# WiFi.net
KiCad netlist of a schematic drawn in Altium Designer
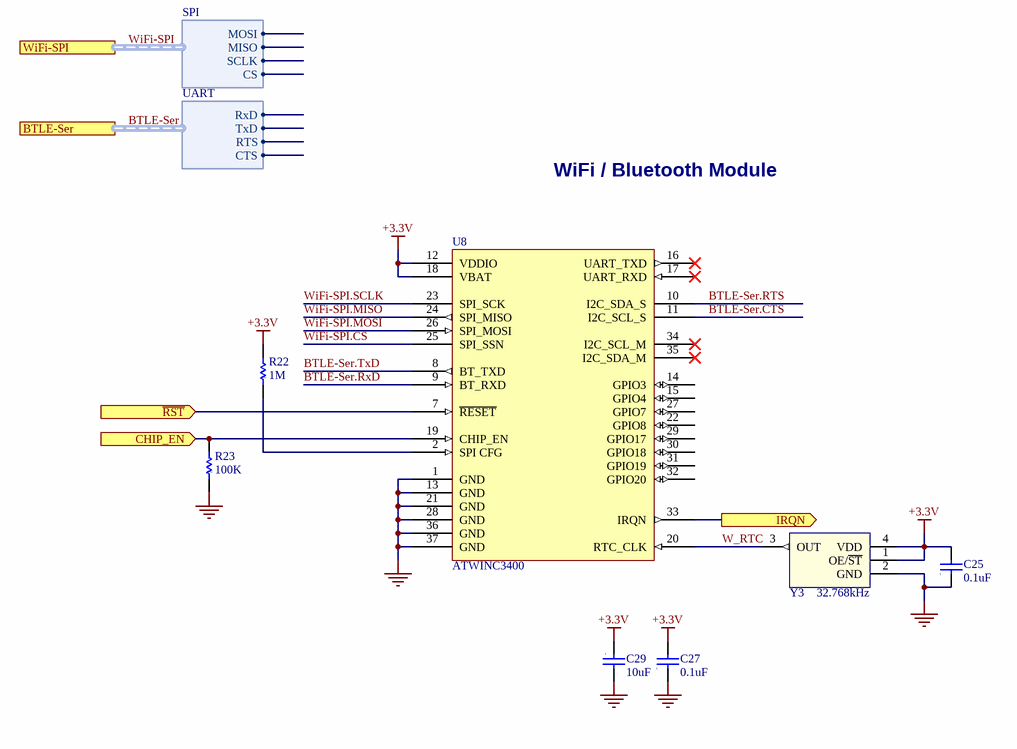
[diagram p0: WiFi.SchDoc]

(export (version "E")
  (design (tool "Eeschema 10.0.6"))
  (components
    (comp (ref "C25")
      (value "0.1uF")
      (footprint "0402")
      (description "CAP CER .10UF 50V X7R 10% 0402")
      (fields
        (field (name "MANUFACTURER") "TDK Corporation")
        (field (name "MANUFACTURER PART NUMBER") "C1005X7R1H104K")
        (field (name "PUBLISHER") "Altium Limited")
      )
      (libsource (lib "") (part "Cap_1"))
    )
    (comp (ref "C27")
      (value "0.1uF")
      (footprint "0402")
      (description "CAP CER .10UF 50V X7R 10% 0402")
      (fields
        (field (name "MANUFACTURER") "TDK Corporation")
        (field (name "MANUFACTURER PART NUMBER") "C1005X7R1H104K")
        (field (name "PUBLISHER") "Altium Limited")
      )
      (libsource (lib "") (part "Cap_1"))
    )
    (comp (ref "C29")
      (value "10uF")
      (footprint "0805")
      (description "CAP CER 10UF 35V X5R 0805")
      (fields
        (field (name "MANUFACTURER") "TDK")
        (field (name "MANUFACTURER PART NUMBER") "C2012X5R1V106K085AC")
        (field (name "PUBLISHER") "Altium Limited")
      )
      (libsource (lib "General") (part "Cap"))
    )
    (comp (ref "R22")
      (value "1M")
      (footprint "R0402")
      (description "RES SMD 1M OHM 5% 1/10W 0402")
      (fields
        (field (name "MANUFACTURER") "Panasonic")
        (field (name "MANUFACTURER PART NUMBER") "ERJ-2GEJ105X")
      )
      (libsource (lib "General") (part "Res"))
    )
    (comp (ref "R23")
      (value "100K")
      (footprint "R0402")
      (description "RES SMD 100K OHM 1% 1/16W 0402")
      (fields
        (field (name "MANUFACTURER") "Panasonic")
        (field (name "MANUFACTURER PART NUMBER") "ERJ-2RKF1003X")
      )
      (libsource (lib "General") (part "Res"))
    )
    (comp (ref "U8")
      (value "ATWINC3400")
      (footprint "ATWILC3000")
      (description "WIFI/BLE MODULE")
      (fields
        (field (name "MANUFACTURER") "Microchip")
        (field (name "MANUFACTURER PART NUMBER") "ATWINC3400-MR210UA122")
      )
      (libsource (lib "General") (part "ATWINC3400"))
    )
    (comp (ref "Y3")
      (value "Oscillator2")
      (footprint "SiT1533")
      (description "OSC MEMS 32.768KHZ LVCMOS SMD")
      (fields
        (field (name "MANUFACTURER") "SiTime")
        (field (name "MANUFACTURER PART NUMBER") "SIT1533AI-H4-DCC-32.768E")
        (field (name "FREQUENCY") "32.768kHz")
      )
      (libsource (lib "General") (part "Oscillator2"))
    )
  )
  (nets
    (net (code "3") (name "+3.3V") (class "Default")
      (node (ref "C25") (pin "2") (pinfunction "2_2") (pintype "passive"))
      (node (ref "C27") (pin "2") (pinfunction "2_2") (pintype "passive"))
      (node (ref "C29") (pin "1") (pinfunction "1_1") (pintype "passive"))
      (node (ref "R22") (pin "2") (pinfunction "2_2") (pintype "passive"))
      (node (ref "U8") (pin "12") (pinfunction "VDDIO_12") (pintype "power_in"))
      (node (ref "U8") (pin "18") (pinfunction "VBAT_18") (pintype "power_in"))
      (node (ref "Y3") (pin "1") (pinfunction "OE/~{ST}_1") (pintype "passive"))
      (node (ref "Y3") (pin "4") (pinfunction "VDD_4") (pintype "passive"))
    )
    (net (code "4") (name "/BTLE-Ser.CTS") (class "Default")
      (node (ref "U8") (pin "11") (pinfunction "I2C_SCL_S_11") (pintype "passive"))
    )
    (net (code "5") (name "/BTLE-Ser.RTS") (class "Default")
      (node (ref "U8") (pin "10") (pinfunction "I2C_SDA_S_10") (pintype "passive"))
    )
    (net (code "6") (name "/BTLE-Ser.RxD") (class "Default")
      (node (ref "U8") (pin "9") (pinfunction "BT_RXD_9") (pintype "input"))
    )
    (net (code "7") (name "/BTLE-Ser.TxD") (class "Default")
      (node (ref "U8") (pin "8") (pinfunction "BT_TXD_8") (pintype "output"))
    )
    (net (code "9") (name "/CHIP_EN") (class "Default")
      (node (ref "R23") (pin "2") (pinfunction "2_2") (pintype "passive"))
      (node (ref "U8") (pin "19") (pinfunction "CHIP_EN_19") (pintype "input"))
    )
    (net (code "10") (name "/IRQN") (class "Default")
      (node (ref "U8") (pin "33") (pinfunction "IRQN_33") (pintype "output"))
    )
    (net (code "11") (name "/RST") (class "Default")
      (node (ref "U8") (pin "7") (pinfunction "RESET_7") (pintype "input"))
    )
    (net (code "12") (name "/W_RTC") (class "Default")
      (node (ref "U8") (pin "20") (pinfunction "RTC_CLK_20") (pintype "input"))
      (node (ref "Y3") (pin "3") (pinfunction "OUT_3") (pintype "output"))
    )
    (net (code "13") (name "/WiFi-SPI.CS") (class "Default")
      (node (ref "U8") (pin "25") (pinfunction "SPI_SSN_25") (pintype "passive"))
    )
    (net (code "14") (name "/WiFi-SPI.MISO") (class "Default")
      (node (ref "U8") (pin "24") (pinfunction "SPI_MISO_24") (pintype "output"))
    )
    (net (code "15") (name "/WiFi-SPI.MOSI") (class "Default")
      (node (ref "U8") (pin "26") (pinfunction "SPI_MOSI_26") (pintype "input"))
    )
    (net (code "16") (name "/WiFi-SPI.SCLK") (class "Default")
      (node (ref "U8") (pin "23") (pinfunction "SPI_SCK_23") (pintype "passive"))
    )
    (net (code "18") (name "GND") (class "Default")
      (node (ref "C25") (pin "1") (pinfunction "1_1") (pintype "passive"))
      (node (ref "C27") (pin "1") (pinfunction "1_1") (pintype "passive"))
      (node (ref "C29") (pin "2") (pinfunction "2_2") (pintype "passive"))
      (node (ref "R23") (pin "1") (pinfunction "1_1") (pintype "passive"))
      (node (ref "U8") (pin "1") (pinfunction "GND_1") (pintype "power_in"))
      (node (ref "U8") (pin "13") (pinfunction "GND_13") (pintype "power_in"))
      (node (ref "U8") (pin "21") (pinfunction "GND_21") (pintype "power_in"))
      (node (ref "U8") (pin "28") (pinfunction "GND_28") (pintype "power_in"))
      (node (ref "U8") (pin "36") (pinfunction "GND_36") (pintype "power_in"))
      (node (ref "U8") (pin "37") (pinfunction "GND_37") (pintype "power_in"))
      (node (ref "Y3") (pin "2") (pinfunction "GND_2") (pintype "passive"))
    )
    (net (code "19") (name "Net-(U8-SPI_CFG)") (class "Default")
      (node (ref "R22") (pin "1") (pinfunction "1_1") (pintype "passive"))
      (node (ref "U8") (pin "2") (pinfunction "SPI_CFG_2") (pintype "input"))
    )
    (net (code "20") (name "unconnected-(U8-GPIO3-Pad14)") (class "Default")
      (node (ref "U8") (pin "14") (pinfunction "GPIO3_14") (pintype "bidirectional"))
    )
    (net (code "21") (name "unconnected-(U8-GPIO4-Pad15)") (class "Default")
      (node (ref "U8") (pin "15") (pinfunction "GPIO4_15") (pintype "bidirectional"))
    )
    (net (code "22") (name "unconnected-(U8-GPIO7-Pad27)") (class "Default")
      (node (ref "U8") (pin "27") (pinfunction "GPIO7_27") (pintype "bidirectional"))
    )
    (net (code "23") (name "unconnected-(U8-GPIO8-Pad22)") (class "Default")
      (node (ref "U8") (pin "22") (pinfunction "GPIO8_22") (pintype "bidirectional"))
    )
    (net (code "24") (name "unconnected-(U8-GPIO17-Pad29)") (class "Default")
      (node (ref "U8") (pin "29") (pinfunction "GPIO17_29") (pintype "bidirectional"))
    )
    (net (code "25") (name "unconnected-(U8-GPIO18-Pad30)") (class "Default")
      (node (ref "U8") (pin "30") (pinfunction "GPIO18_30") (pintype "bidirectional"))
    )
    (net (code "26") (name "unconnected-(U8-GPIO19-Pad31)") (class "Default")
      (node (ref "U8") (pin "31") (pinfunction "GPIO19_31") (pintype "bidirectional"))
    )
    (net (code "27") (name "unconnected-(U8-GPIO20-Pad32)") (class "Default")
      (node (ref "U8") (pin "32") (pinfunction "GPIO20_32") (pintype "bidirectional"))
    )
    (net (code "28") (name "unconnected-(U8-I2C_SCL_M-Pad34)") (class "Default")
      (node (ref "U8") (pin "34") (pinfunction "I2C_SCL_M_34") (pintype "passive+no_connect"))
    )
    (net (code "29") (name "unconnected-(U8-I2C_SDA_M-Pad35)") (class "Default")
      (node (ref "U8") (pin "35") (pinfunction "I2C_SDA_M_35") (pintype "passive+no_connect"))
    )
    (net (code "30") (name "unconnected-(U8-UART_RXD-Pad17)") (class "Default")
      (node (ref "U8") (pin "17") (pinfunction "UART_RXD_17") (pintype "input+no_connect"))
    )
    (net (code "31") (name "unconnected-(U8-UART_TXD-Pad16)") (class "Default")
      (node (ref "U8") (pin "16") (pinfunction "UART_TXD_16") (pintype "output+no_connect"))
    )
  )
)
